# LightToFreq.net
KiCad netlist of a schematic drawn in EAGLE
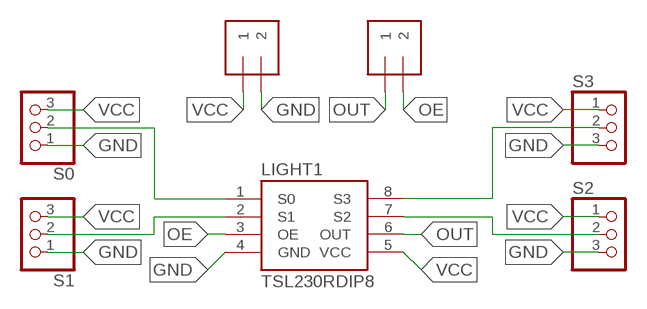
[diagram p0: schematic, sheet 1]

(export (version "E")
  (design (tool "Eeschema 10.0.6"))
  (components
    (comp (ref "J1")
      (value "1X2-3.5MM")
      (footprint "eagle-import:1X2-3.5MM")
      (libsource (lib "eagle-import") (part "1X2-3.5MM"))
    )
    (comp (ref "J2")
      (value "1X2-3.5MM")
      (footprint "eagle-import:1X2-3.5MM")
      (libsource (lib "eagle-import") (part "1X2-3.5MM"))
    )
    (comp (ref "LIGHT1")
      (value "TSL230RDIP8")
      (footprint "eagle-import:DIP8")
      (libsource (lib "eagle-import") (part "TSL230RDIP8"))
    )
    (comp (ref "S0")
      (value "PINHD-1X3CB")
      (footprint "eagle-import:1X03-CLEANBIG")
      (libsource (lib "eagle-import") (part "PINHD-1X3CB"))
    )
    (comp (ref "S1")
      (value "PINHD-1X3CB")
      (footprint "eagle-import:1X03-CLEANBIG")
      (libsource (lib "eagle-import") (part "PINHD-1X3CB"))
    )
    (comp (ref "S2")
      (value "PINHD-1X3CB")
      (footprint "eagle-import:1X03-CLEANBIG")
      (libsource (lib "eagle-import") (part "PINHD-1X3CB"))
    )
    (comp (ref "S3")
      (value "PINHD-1X3CB")
      (footprint "eagle-import:1X03-CLEANBIG")
      (libsource (lib "eagle-import") (part "PINHD-1X3CB"))
    )
  )
  (nets
    (net (code "1") (name "GND") (class "Default")
      (node (ref "J1") (pin "2") (pinfunction "2_2") (pintype "passive"))
      (node (ref "LIGHT1") (pin "4") (pinfunction "GND_4") (pintype "power_in"))
      (node (ref "S0") (pin "1") (pinfunction "1_1") (pintype "passive"))
      (node (ref "S1") (pin "1") (pinfunction "1_1") (pintype "passive"))
      (node (ref "S2") (pin "3") (pinfunction "3_3") (pintype "passive"))
      (node (ref "S3") (pin "3") (pinfunction "3_3") (pintype "passive"))
    )
    (net (code "2") (name "Net-(LIGHT1-S0)") (class "Default")
      (node (ref "LIGHT1") (pin "1") (pinfunction "S0_1") (pintype "bidirectional"))
      (node (ref "S0") (pin "2") (pinfunction "2_2") (pintype "passive"))
    )
    (net (code "3") (name "Net-(LIGHT1-S1)") (class "Default")
      (node (ref "LIGHT1") (pin "2") (pinfunction "S1_2") (pintype "bidirectional"))
      (node (ref "S1") (pin "2") (pinfunction "2_2") (pintype "passive"))
    )
    (net (code "4") (name "Net-(LIGHT1-S2)") (class "Default")
      (node (ref "LIGHT1") (pin "7") (pinfunction "S2_7") (pintype "bidirectional"))
      (node (ref "S2") (pin "2") (pinfunction "2_2") (pintype "passive"))
    )
    (net (code "5") (name "Net-(LIGHT1-S3)") (class "Default")
      (node (ref "LIGHT1") (pin "8") (pinfunction "S3_8") (pintype "bidirectional"))
      (node (ref "S3") (pin "2") (pinfunction "2_2") (pintype "passive"))
    )
    (net (code "6") (name "OE") (class "Default")
      (node (ref "J2") (pin "2") (pinfunction "2_2") (pintype "passive"))
      (node (ref "LIGHT1") (pin "3") (pinfunction "OE_3") (pintype "power_in"))
    )
    (net (code "7") (name "OUT") (class "Default")
      (node (ref "J2") (pin "1") (pinfunction "1_1") (pintype "passive"))
      (node (ref "LIGHT1") (pin "6") (pinfunction "OUT_6") (pintype "bidirectional"))
    )
    (net (code "8") (name "VCC") (class "Default")
      (node (ref "J1") (pin "1") (pinfunction "1_1") (pintype "passive"))
      (node (ref "LIGHT1") (pin "5") (pinfunction "VCC_5") (pintype "bidirectional"))
      (node (ref "S0") (pin "3") (pinfunction "3_3") (pintype "passive"))
      (node (ref "S1") (pin "3") (pinfunction "3_3") (pintype "passive"))
      (node (ref "S2") (pin "1") (pinfunction "1_1") (pintype "passive"))
      (node (ref "S3") (pin "1") (pinfunction "1_1") (pintype "passive"))
    )
  )
)
